# lab442canpowerV2.net
KiCad netlist of a schematic drawn in EasyEDA Pro
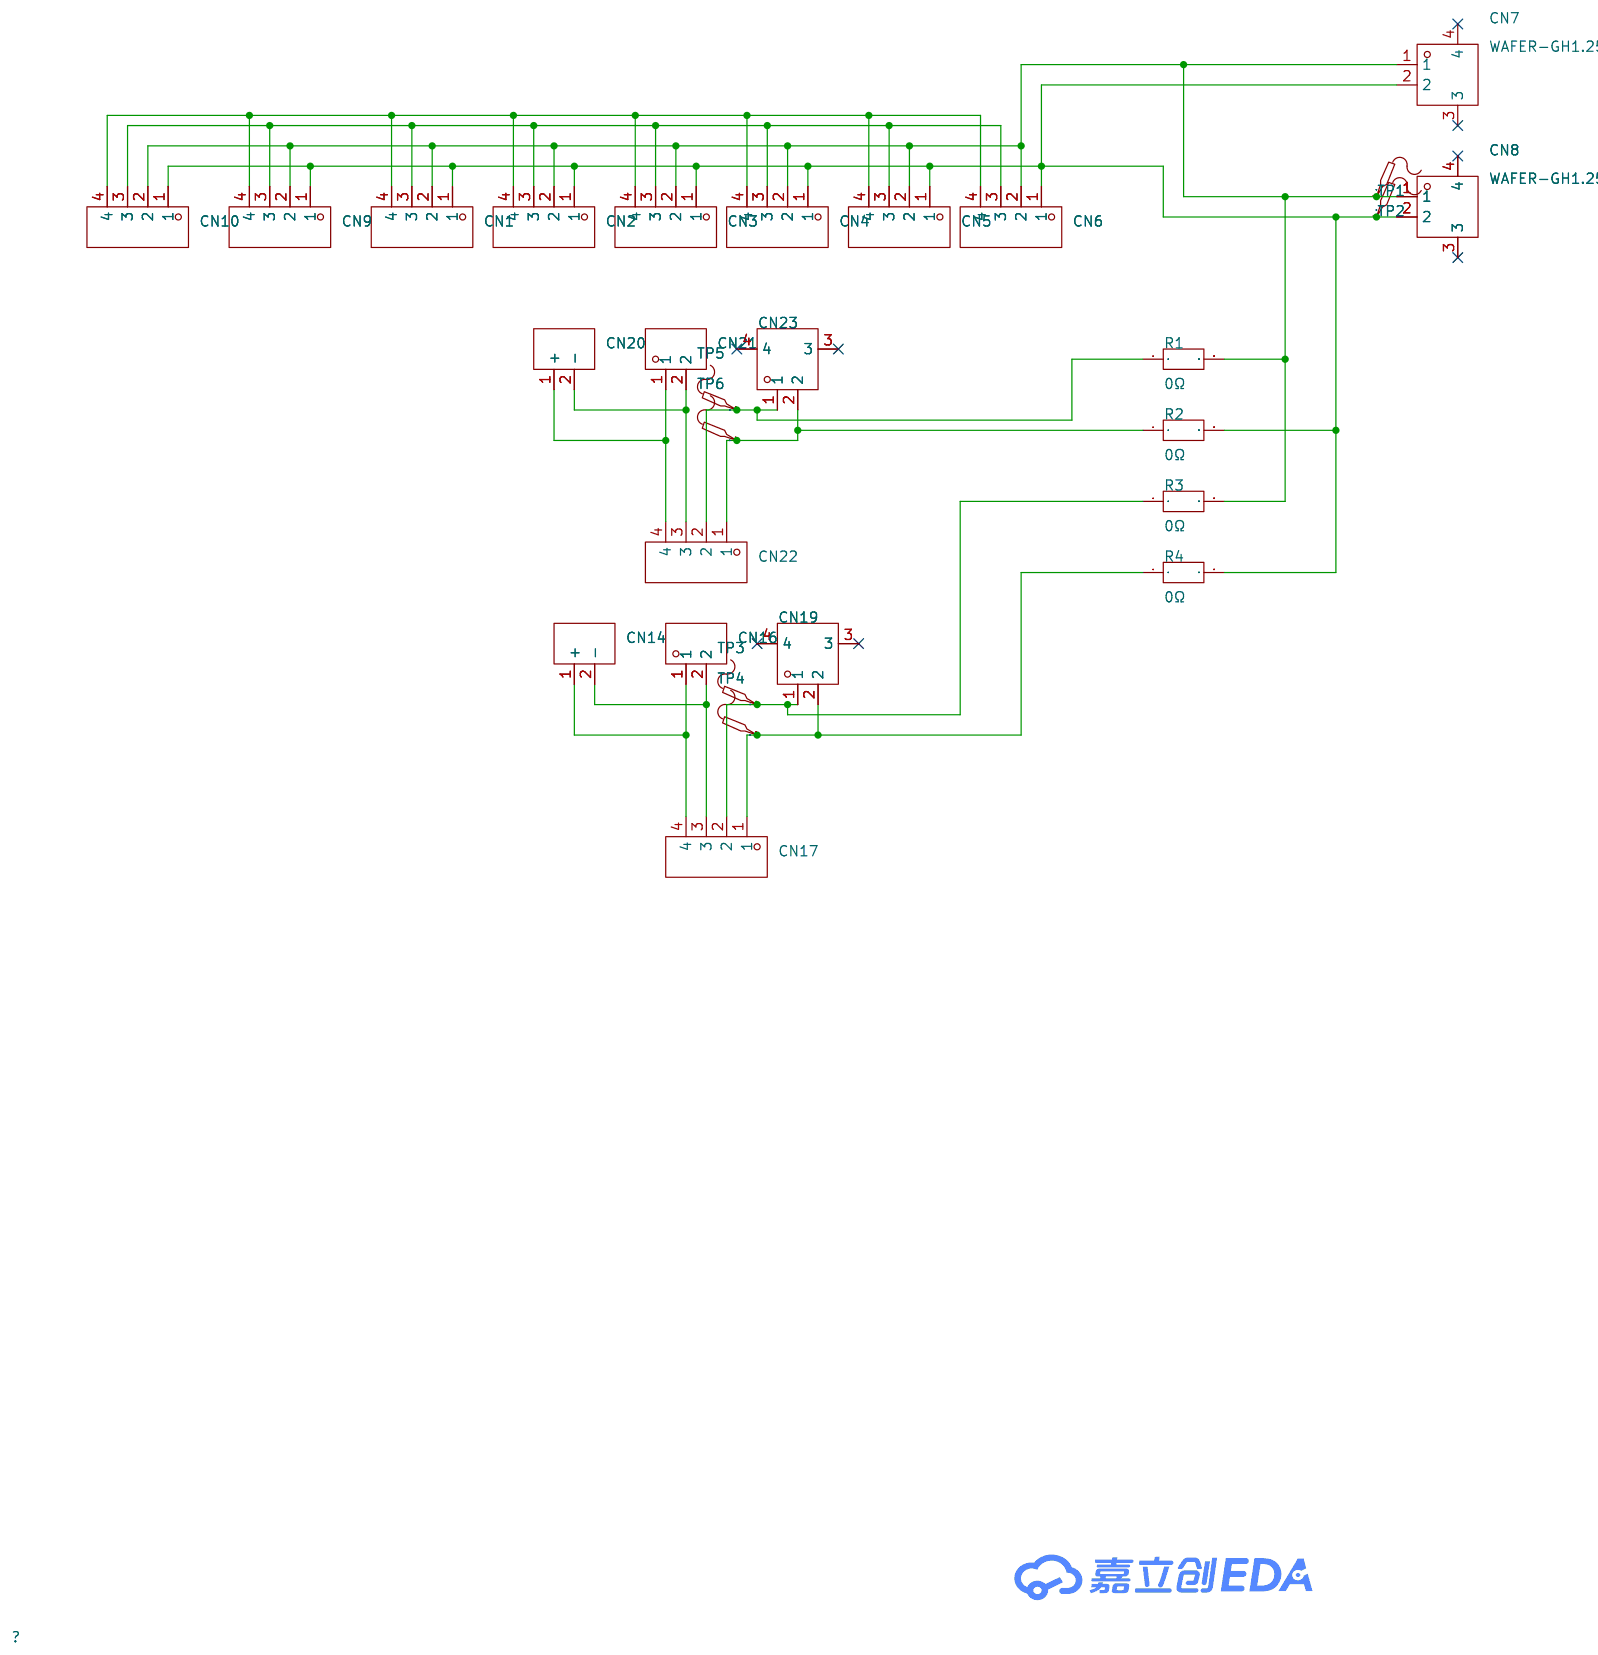
[diagram p0: schematic sheet]

(export (version "E")
  (design (tool "Eeschema 10.0.6"))
  (components
    (comp (ref "CN1")
      (value "XT30(2+2)PB-M.G.B")
      (footprint "easyedapro:CONN-TH_XT30PB-M")
      (fields (field (name "Manufacturer") "AMASS(艾迈斯)"))
      (libsource (lib "easyedapro") (part "XT30(2+2)PB-M.G.B"))
    )
    (comp (ref "CN2")
      (value "XT30(2+2)PB-M.G.B")
      (footprint "easyedapro:CONN-TH_XT30PB-M")
      (fields (field (name "Manufacturer") "AMASS(艾迈斯)"))
      (libsource (lib "easyedapro") (part "XT30(2+2)PB-M.G.B"))
    )
    (comp (ref "CN3")
      (value "XT30(2+2)PB-M.G.B")
      (footprint "easyedapro:CONN-TH_XT30PB-M")
      (fields (field (name "Manufacturer") "AMASS(艾迈斯)"))
      (libsource (lib "easyedapro") (part "XT30(2+2)PB-M.G.B"))
    )
    (comp (ref "CN4")
      (value "XT30(2+2)PB-M.G.B")
      (footprint "easyedapro:CONN-TH_XT30PB-M")
      (fields (field (name "Manufacturer") "AMASS(艾迈斯)"))
      (libsource (lib "easyedapro") (part "XT30(2+2)PB-M.G.B"))
    )
    (comp (ref "CN5")
      (value "XT30(2+2)PB-M.G.B")
      (footprint "easyedapro:CONN-TH_XT30PB-M")
      (fields (field (name "Manufacturer") "AMASS(艾迈斯)"))
      (libsource (lib "easyedapro") (part "XT30(2+2)PB-M.G.B"))
    )
    (comp (ref "CN6")
      (value "XT30(2+2)PB-M.G.B")
      (footprint "easyedapro:CONN-TH_XT30PB-M")
      (fields (field (name "Manufacturer") "AMASS(艾迈斯)"))
      (libsource (lib "easyedapro") (part "XT30(2+2)PB-M.G.B"))
    )
    (comp (ref "CN7")
      (value "WAFER-GH1.25-2PWB")
      (footprint "easyedapro:CONN-TH_2P-P1.25_XUNPU_WAFER-GH1.25-2PWB")
      (fields (field (name "Manufacturer") "XUNPU(讯普)"))
      (libsource (lib "easyedapro") (part "WAFER-GH1.25-2PWB"))
    )
    (comp (ref "CN8")
      (value "WAFER-GH1.25-2PWB")
      (footprint "easyedapro:CONN-TH_2P-P1.25_XUNPU_WAFER-GH1.25-2PWB")
      (fields (field (name "Manufacturer") "XUNPU(讯普)"))
      (libsource (lib "easyedapro") (part "WAFER-GH1.25-2PWB"))
    )
    (comp (ref "CN9")
      (value "XT30(2+2)PB-M.G.B")
      (footprint "easyedapro:CONN-TH_XT30PB-M")
      (fields (field (name "Manufacturer") "AMASS(艾迈斯)"))
      (libsource (lib "easyedapro") (part "XT30(2+2)PB-M.G.B"))
    )
    (comp (ref "CN10")
      (value "XT30(2+2)PB-M.G.B")
      (footprint "easyedapro:CONN-TH_XT30PB-M")
      (fields (field (name "Manufacturer") "AMASS(艾迈斯)"))
      (libsource (lib "easyedapro") (part "XT30(2+2)PB-M.G.B"))
    )
    (comp (ref "CN14")
      (value "XT30UPB-F30.G.Y")
      (footprint "easyedapro:CONN-TH_XT30UPB-F")
      (description "类别:-;类型1:-;")
      (fields (field (name "Manufacturer") "AMASS(艾迈斯)"))
      (libsource (lib "easyedapro") (part "XT30UPB-F"))
    )
    (comp (ref "CN16")
      (value "XT30U-M")
      (footprint "easyedapro:CONN-TH_XT30U-M")
      (description "类别:-;类型1:-;")
      (fields (field (name "Manufacturer") "AMASS(艾迈斯)"))
      (libsource (lib "easyedapro") (part "XT30U-M"))
    )
    (comp (ref "CN17")
      (value "XT30(2+2)PB-M.G.B")
      (footprint "easyedapro:CONN-TH_XT30PB-M")
      (fields (field (name "Manufacturer") "AMASS(艾迈斯)"))
      (libsource (lib "easyedapro") (part "XT30(2+2)PB-M.G.B"))
    )
    (comp (ref "CN19")
      (value "WAFER-GH1.25-2PWB")
      (footprint "easyedapro:CONN-TH_2P-P1.25_XUNPU_WAFER-GH1.25-2PWB")
      (fields (field (name "Manufacturer") "XUNPU(讯普)"))
      (libsource (lib "easyedapro") (part "WAFER-GH1.25-2PWB"))
    )
    (comp (ref "CN20")
      (value "XT30UPB-F30.G.Y")
      (footprint "easyedapro:CONN-TH_XT30UPB-F")
      (description "类别:-;类型1:-;")
      (fields (field (name "Manufacturer") "AMASS(艾迈斯)"))
      (libsource (lib "easyedapro") (part "XT30UPB-F"))
    )
    (comp (ref "CN21")
      (value "XT30U-M")
      (footprint "easyedapro:CONN-TH_XT30U-M")
      (description "类别:-;类型1:-;")
      (fields (field (name "Manufacturer") "AMASS(艾迈斯)"))
      (libsource (lib "easyedapro") (part "XT30U-M"))
    )
    (comp (ref "CN22")
      (value "XT30(2+2)PB-M.G.B")
      (footprint "easyedapro:CONN-TH_XT30PB-M")
      (fields (field (name "Manufacturer") "AMASS(艾迈斯)"))
      (libsource (lib "easyedapro") (part "XT30(2+2)PB-M.G.B"))
    )
    (comp (ref "CN23")
      (value "WAFER-GH1.25-2PWB")
      (footprint "easyedapro:CONN-TH_2P-P1.25_XUNPU_WAFER-GH1.25-2PWB")
      (fields (field (name "Manufacturer") "XUNPU(讯普)"))
      (libsource (lib "easyedapro") (part "WAFER-GH1.25-2PWB"))
    )
    (comp (ref "R1")
      (value "0Ω")
      (footprint "easyedapro:RES-SMD_L6.4-W3.2-A")
      (description "电阻类型:采样电阻;阻值:0Ω;精度:±1%;功率:3W;")
      (fields (field (name "Manufacturer Part") "RE2512F3R000L") (field (name "Manufacturer") "捷而瑞"))
      (libsource (lib "easyedapro") (part "RE2512F3R000L"))
    )
    (comp (ref "R2")
      (value "0Ω")
      (footprint "easyedapro:RES-SMD_L6.4-W3.2-A")
      (description "电阻类型:采样电阻;阻值:0Ω;精度:±1%;功率:3W;")
      (fields (field (name "Manufacturer Part") "RE2512F3R000L") (field (name "Manufacturer") "捷而瑞"))
      (libsource (lib "easyedapro") (part "RE2512F3R000L"))
    )
    (comp (ref "R3")
      (value "0Ω")
      (footprint "easyedapro:RES-SMD_L6.4-W3.2-A")
      (description "电阻类型:采样电阻;阻值:0Ω;精度:±1%;功率:3W;")
      (fields (field (name "Manufacturer Part") "RE2512F3R000L") (field (name "Manufacturer") "捷而瑞"))
      (libsource (lib "easyedapro") (part "RE2512F3R000L"))
    )
    (comp (ref "R4")
      (value "0Ω")
      (footprint "easyedapro:RES-SMD_L6.4-W3.2-A")
      (description "电阻类型:采样电阻;阻值:0Ω;精度:±1%;功率:3W;")
      (fields (field (name "Manufacturer Part") "RE2512F3R000L") (field (name "Manufacturer") "捷而瑞"))
      (libsource (lib "easyedapro") (part "RE2512F3R000L"))
    )
    (comp (ref "TP1")
      (value "~")
      (footprint "easyedapro:Test-Point-0.5mm")
      (description "Test Point 测试点")
      (libsource (lib "easyedapro") (part "Test-Point"))
    )
    (comp (ref "TP2")
      (value "~")
      (footprint "easyedapro:Test-Point-0.5mm")
      (description "Test Point 测试点")
      (libsource (lib "easyedapro") (part "Test-Point"))
    )
    (comp (ref "TP3")
      (value "~")
      (footprint "easyedapro:Test-Point-0.5mm")
      (description "Test Point 测试点")
      (libsource (lib "easyedapro") (part "Test-Point"))
    )
    (comp (ref "TP4")
      (value "~")
      (footprint "easyedapro:Test-Point-0.5mm")
      (description "Test Point 测试点")
      (libsource (lib "easyedapro") (part "Test-Point"))
    )
    (comp (ref "TP5")
      (value "~")
      (footprint "easyedapro:Test-Point-0.5mm")
      (description "Test Point 测试点")
      (libsource (lib "easyedapro") (part "Test-Point"))
    )
    (comp (ref "TP6")
      (value "~")
      (footprint "easyedapro:Test-Point-0.5mm")
      (description "Test Point 测试点")
      (libsource (lib "easyedapro") (part "Test-Point"))
    )
  )
  (nets
    (net (code "1") (name "Net-(CN1-Pad1)") (class "Default")
      (node (ref "CN1") (pin "1") (pinfunction "1_1") (pintype "unspecified"))
      (node (ref "CN10") (pin "1") (pinfunction "1_1") (pintype "unspecified"))
      (node (ref "CN2") (pin "1") (pinfunction "1_1") (pintype "unspecified"))
      (node (ref "CN3") (pin "1") (pinfunction "1_1") (pintype "unspecified"))
      (node (ref "CN4") (pin "1") (pinfunction "1_1") (pintype "unspecified"))
      (node (ref "CN5") (pin "1") (pinfunction "1_1") (pintype "unspecified"))
      (node (ref "CN6") (pin "1") (pinfunction "1_1") (pintype "unspecified"))
      (node (ref "CN7") (pin "2") (pinfunction "2_2") (pintype "unspecified"))
      (node (ref "CN8") (pin "2") (pinfunction "2_2") (pintype "unspecified"))
      (node (ref "CN9") (pin "1") (pinfunction "1_1") (pintype "unspecified"))
      (node (ref "R2") (pin "2") (pinfunction "2_2") (pintype "unspecified"))
      (node (ref "R4") (pin "2") (pinfunction "2_2") (pintype "unspecified"))
      (node (ref "TP2") (pin "1") (pinfunction "1_1") (pintype "input"))
    )
    (net (code "2") (name "Net-(CN1-Pad2)") (class "Default")
      (node (ref "CN1") (pin "2") (pinfunction "2_2") (pintype "unspecified"))
      (node (ref "CN10") (pin "2") (pinfunction "2_2") (pintype "unspecified"))
      (node (ref "CN2") (pin "2") (pinfunction "2_2") (pintype "unspecified"))
      (node (ref "CN3") (pin "2") (pinfunction "2_2") (pintype "unspecified"))
      (node (ref "CN4") (pin "2") (pinfunction "2_2") (pintype "unspecified"))
      (node (ref "CN5") (pin "2") (pinfunction "2_2") (pintype "unspecified"))
      (node (ref "CN6") (pin "2") (pinfunction "2_2") (pintype "unspecified"))
      (node (ref "CN7") (pin "1") (pinfunction "1_1") (pintype "unspecified"))
      (node (ref "CN8") (pin "1") (pinfunction "1_1") (pintype "unspecified"))
      (node (ref "CN9") (pin "2") (pinfunction "2_2") (pintype "unspecified"))
      (node (ref "R1") (pin "2") (pinfunction "2_2") (pintype "unspecified"))
      (node (ref "R3") (pin "2") (pinfunction "2_2") (pintype "unspecified"))
      (node (ref "TP1") (pin "1") (pinfunction "1_1") (pintype "input"))
    )
    (net (code "3") (name "Net-(CN1-Pad3)") (class "Default")
      (node (ref "CN1") (pin "3") (pinfunction "3_3") (pintype "unspecified"))
      (node (ref "CN10") (pin "3") (pinfunction "3_3") (pintype "unspecified"))
      (node (ref "CN2") (pin "3") (pinfunction "3_3") (pintype "unspecified"))
      (node (ref "CN3") (pin "3") (pinfunction "3_3") (pintype "unspecified"))
      (node (ref "CN4") (pin "3") (pinfunction "3_3") (pintype "unspecified"))
      (node (ref "CN5") (pin "3") (pinfunction "3_3") (pintype "unspecified"))
      (node (ref "CN6") (pin "3") (pinfunction "3_3") (pintype "unspecified"))
      (node (ref "CN9") (pin "3") (pinfunction "3_3") (pintype "unspecified"))
    )
    (net (code "4") (name "Net-(CN1-Pad4)") (class "Default")
      (node (ref "CN1") (pin "4") (pinfunction "4_4") (pintype "unspecified"))
      (node (ref "CN10") (pin "4") (pinfunction "4_4") (pintype "unspecified"))
      (node (ref "CN2") (pin "4") (pinfunction "4_4") (pintype "unspecified"))
      (node (ref "CN3") (pin "4") (pinfunction "4_4") (pintype "unspecified"))
      (node (ref "CN4") (pin "4") (pinfunction "4_4") (pintype "unspecified"))
      (node (ref "CN5") (pin "4") (pinfunction "4_4") (pintype "unspecified"))
      (node (ref "CN6") (pin "4") (pinfunction "4_4") (pintype "unspecified"))
      (node (ref "CN9") (pin "4") (pinfunction "4_4") (pintype "unspecified"))
    )
    (net (code "5") (name "Net-(CN14-+)") (class "Default")
      (node (ref "CN14") (pin "1") (pinfunction "+_1") (pintype "unspecified"))
      (node (ref "CN16") (pin "1") (pinfunction "1_1") (pintype "unspecified"))
      (node (ref "CN17") (pin "4") (pinfunction "4_4") (pintype "unspecified"))
    )
    (net (code "6") (name "Net-(CN14--)") (class "Default")
      (node (ref "CN14") (pin "2") (pinfunction "-_2") (pintype "unspecified"))
      (node (ref "CN16") (pin "2") (pinfunction "2_2") (pintype "unspecified"))
      (node (ref "CN17") (pin "3") (pinfunction "3_3") (pintype "unspecified"))
    )
    (net (code "7") (name "Net-(CN17-Pad1)") (class "Default")
      (node (ref "CN17") (pin "1") (pinfunction "1_1") (pintype "unspecified"))
      (node (ref "CN19") (pin "2") (pinfunction "2_2") (pintype "unspecified"))
      (node (ref "R4") (pin "1") (pinfunction "1_1") (pintype "unspecified"))
      (node (ref "TP4") (pin "1") (pinfunction "1_1") (pintype "input"))
    )
    (net (code "8") (name "Net-(CN17-Pad2)") (class "Default")
      (node (ref "CN17") (pin "2") (pinfunction "2_2") (pintype "unspecified"))
      (node (ref "CN19") (pin "1") (pinfunction "1_1") (pintype "unspecified"))
      (node (ref "R3") (pin "1") (pinfunction "1_1") (pintype "unspecified"))
      (node (ref "TP3") (pin "1") (pinfunction "1_1") (pintype "input"))
    )
    (net (code "9") (name "Net-(CN20-+)") (class "Default")
      (node (ref "CN20") (pin "1") (pinfunction "+_1") (pintype "unspecified"))
      (node (ref "CN21") (pin "1") (pinfunction "1_1") (pintype "unspecified"))
      (node (ref "CN22") (pin "4") (pinfunction "4_4") (pintype "unspecified"))
    )
    (net (code "10") (name "Net-(CN20--)") (class "Default")
      (node (ref "CN20") (pin "2") (pinfunction "-_2") (pintype "unspecified"))
      (node (ref "CN21") (pin "2") (pinfunction "2_2") (pintype "unspecified"))
      (node (ref "CN22") (pin "3") (pinfunction "3_3") (pintype "unspecified"))
    )
    (net (code "11") (name "Net-(CN22-Pad1)") (class "Default")
      (node (ref "CN22") (pin "1") (pinfunction "1_1") (pintype "unspecified"))
      (node (ref "CN23") (pin "2") (pinfunction "2_2") (pintype "unspecified"))
      (node (ref "R2") (pin "1") (pinfunction "1_1") (pintype "unspecified"))
      (node (ref "TP6") (pin "1") (pinfunction "1_1") (pintype "input"))
    )
    (net (code "12") (name "Net-(CN22-Pad2)") (class "Default")
      (node (ref "CN22") (pin "2") (pinfunction "2_2") (pintype "unspecified"))
      (node (ref "CN23") (pin "1") (pinfunction "1_1") (pintype "unspecified"))
      (node (ref "R1") (pin "1") (pinfunction "1_1") (pintype "unspecified"))
      (node (ref "TP5") (pin "1") (pinfunction "1_1") (pintype "input"))
    )
    (net (code "13") (name "unconnected-(CN7-Pad3)") (class "Default")
      (node (ref "CN7") (pin "3") (pinfunction "3_3") (pintype "unspecified+no_connect"))
    )
    (net (code "14") (name "unconnected-(CN7-Pad4)") (class "Default")
      (node (ref "CN7") (pin "4") (pinfunction "4_4") (pintype "unspecified+no_connect"))
    )
    (net (code "15") (name "unconnected-(CN8-Pad3)") (class "Default")
      (node (ref "CN8") (pin "3") (pinfunction "3_3") (pintype "unspecified+no_connect"))
    )
    (net (code "16") (name "unconnected-(CN8-Pad4)") (class "Default")
      (node (ref "CN8") (pin "4") (pinfunction "4_4") (pintype "unspecified+no_connect"))
    )
    (net (code "17") (name "unconnected-(CN19-Pad3)") (class "Default")
      (node (ref "CN19") (pin "3") (pinfunction "3_3") (pintype "unspecified+no_connect"))
    )
    (net (code "18") (name "unconnected-(CN19-Pad4)") (class "Default")
      (node (ref "CN19") (pin "4") (pinfunction "4_4") (pintype "unspecified+no_connect"))
    )
    (net (code "19") (name "unconnected-(CN23-Pad3)") (class "Default")
      (node (ref "CN23") (pin "3") (pinfunction "3_3") (pintype "unspecified+no_connect"))
    )
    (net (code "20") (name "unconnected-(CN23-Pad4)") (class "Default")
      (node (ref "CN23") (pin "4") (pinfunction "4_4") (pintype "unspecified+no_connect"))
    )
  )
)
